# Power.net
KiCad netlist of a schematic drawn in Altium Designer
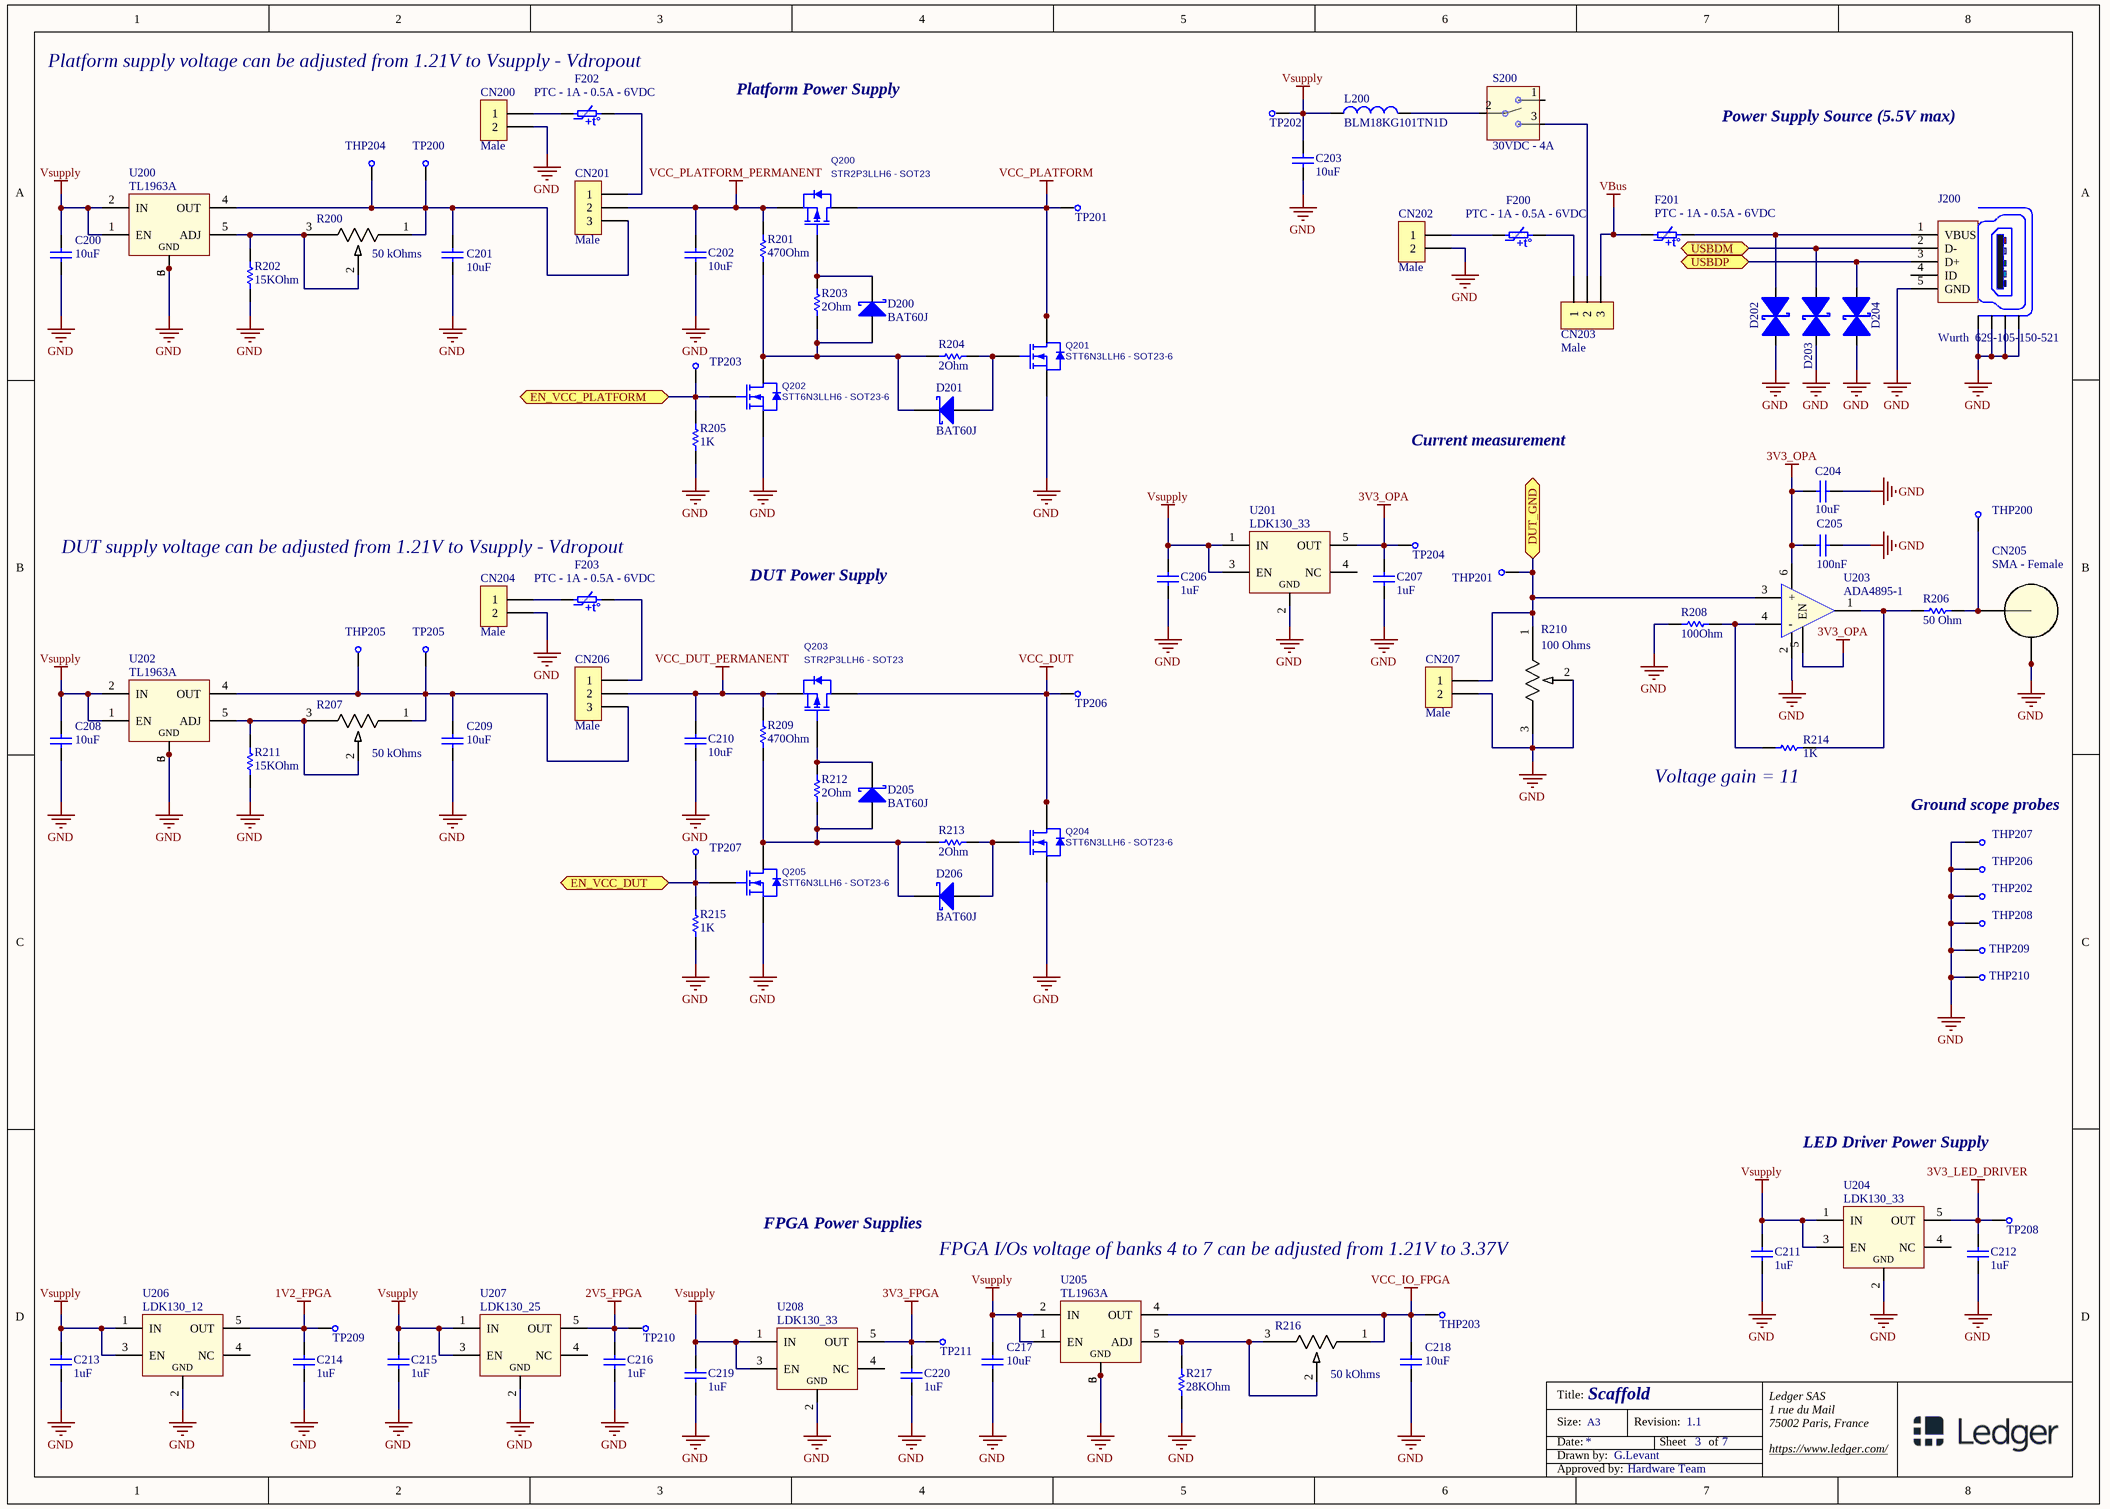
[diagram p0: Power.SchDoc]

(export (version "E")
  (design (tool "Eeschema 10.0.6"))
  (components
    (comp (ref "C200")
      (value "10uF")
      (footprint "CAP0603")
      (description "Capacitor 0603 - 10uF - 16V - X5R - 20%")
      (fields (field (name "MANUFACTURER") "Murata") (field (name "POWER") "16V"))
      (libsource (lib "Ledger_Prod") (part "Capacitor 0603 - 10uF - 16V - X5R - 20%"))
    )
    (comp (ref "C201")
      (value "10uF")
      (footprint "CAP0603")
      (description "Capacitor 0603 - 10uF - 16V - X5R - 20%")
      (fields (field (name "MANUFACTURER") "Murata") (field (name "POWER") "16V"))
      (libsource (lib "Ledger_Prod") (part "Capacitor 0603 - 10uF - 16V - X5R - 20%"))
    )
    (comp (ref "C202")
      (value "10uF")
      (footprint "CAP0603")
      (description "Capacitor 0603 - 10uF - 16V - X5R - 20%")
      (fields (field (name "MANUFACTURER") "Murata") (field (name "TOLERANCE") "20%"))
      (libsource (lib "Ledger_Prod") (part "Capacitor 0603 - 10uF - 16V - X5R - 20%"))
    )
    (comp (ref "C203")
      (value "10uF")
      (footprint "CAP0603")
      (description "Capacitor 0603 - 10uF - 16V - X5R - 20%")
      (fields (field (name "MANUFACTURER") "Murata") (field (name "TOLERANCE") "20%"))
      (libsource (lib "Ledger_Prod") (part "Capacitor 0603 - 10uF - 16V - X5R - 20%"))
    )
    (comp (ref "C204")
      (value "10uF")
      (footprint "CAP0603")
      (description "Capacitor 0603 - 10uF - 16V - X5R - 20%")
      (fields (field (name "MANUFACTURER") "Murata") (field (name "TOLERANCE") "20%"))
      (libsource (lib "Ledger_Prod") (part "Capacitor 0603 - 10uF - 16V - X5R - 20%"))
    )
    (comp (ref "C205")
      (value "100nF")
      (footprint "CAP0603")
      (description "Capacitor 0603 - 100nF - 16V - X7R - 10%")
      (fields (field (name "POWER") "16V") (field (name "TOLERANCE") "10%"))
      (libsource (lib "Ledger_Prod") (part "Capacitor 0603 - 100nF - 16V - X7R - 10%"))
    )
    (comp (ref "C206")
      (value "1uF")
      (footprint "CAP0603")
      (description "Capacitor 0603 - 1uF - 16V - X7R - 10%")
      (fields (field (name "MANUFACTURER") "Kemet") (field (name "POWER") "16V"))
      (libsource (lib "Ledger_Prod") (part "Capacitor 0603 -     1uF - 16V - X7R - 10%"))
    )
    (comp (ref "C207")
      (value "1uF")
      (footprint "CAP0603")
      (description "Capacitor 0603 - 1uF - 16V - X7R - 10%")
      (fields (field (name "MANUFACTURER") "Kemet") (field (name "POWER") "16V"))
      (libsource (lib "Ledger_Prod") (part "Capacitor 0603 -     1uF - 16V - X7R - 10%"))
    )
    (comp (ref "C208")
      (value "10uF")
      (footprint "CAP0603")
      (description "Capacitor 0603 - 10uF - 16V - X5R - 20%")
      (fields (field (name "MANUFACTURER") "Murata") (field (name "POWER") "16V"))
      (libsource (lib "Ledger_Prod") (part "Capacitor 0603 - 10uF - 16V - X5R - 20%"))
    )
    (comp (ref "C209")
      (value "10uF")
      (footprint "CAP0603")
      (description "Capacitor 0603 - 10uF - 16V - X5R - 20%")
      (fields (field (name "MANUFACTURER") "Murata") (field (name "POWER") "16V"))
      (libsource (lib "Ledger_Prod") (part "Capacitor 0603 - 10uF - 16V - X5R - 20%"))
    )
    (comp (ref "C210")
      (value "10uF")
      (footprint "CAP0603")
      (description "Capacitor 0603 - 10uF - 16V - X5R - 20%")
      (fields (field (name "MANUFACTURER") "Murata") (field (name "TOLERANCE") "20%"))
      (libsource (lib "Ledger_Prod") (part "Capacitor 0603 - 10uF - 16V - X5R - 20%"))
    )
    (comp (ref "C211")
      (value "1uF")
      (footprint "CAP0603")
      (description "Capacitor 0603 - 1uF - 16V - X7R - 10%")
      (fields (field (name "MANUFACTURER") "Kemet") (field (name "POWER") "16V"))
      (libsource (lib "Ledger_Prod") (part "Capacitor 0603 -     1uF - 16V - X7R - 10%"))
    )
    (comp (ref "C212")
      (value "1uF")
      (footprint "CAP0603")
      (description "Capacitor 0603 - 1uF - 16V - X7R - 10%")
      (fields (field (name "MANUFACTURER") "Kemet") (field (name "POWER") "16V"))
      (libsource (lib "Ledger_Prod") (part "Capacitor 0603 -     1uF - 16V - X7R - 10%"))
    )
    (comp (ref "C213")
      (value "1uF")
      (footprint "CAP0603")
      (description "Capacitor 0603 - 1uF - 16V - X7R - 10%")
      (fields (field (name "MANUFACTURER") "Kemet") (field (name "POWER") "16V"))
      (libsource (lib "Ledger_Prod") (part "Capacitor 0603 -     1uF - 16V - X7R - 10%"))
    )
    (comp (ref "C214")
      (value "1uF")
      (footprint "CAP0603")
      (description "Capacitor 0603 - 1uF - 16V - X7R - 10%")
      (fields (field (name "MANUFACTURER") "Kemet") (field (name "POWER") "16V"))
      (libsource (lib "Ledger_Prod") (part "Capacitor 0603 -     1uF - 16V - X7R - 10%"))
    )
    (comp (ref "C215")
      (value "1uF")
      (footprint "CAP0603")
      (description "Capacitor 0603 - 1uF - 16V - X7R - 10%")
      (fields (field (name "MANUFACTURER") "Kemet") (field (name "POWER") "16V"))
      (libsource (lib "Ledger_Prod") (part "Capacitor 0603 -     1uF - 16V - X7R - 10%"))
    )
    (comp (ref "C216")
      (value "1uF")
      (footprint "CAP0603")
      (description "Capacitor 0603 - 1uF - 16V - X7R - 10%")
      (fields (field (name "MANUFACTURER") "Kemet") (field (name "POWER") "16V"))
      (libsource (lib "Ledger_Prod") (part "Capacitor 0603 -     1uF - 16V - X7R - 10%"))
    )
    (comp (ref "C217")
      (value "10uF")
      (footprint "CAP0603")
      (description "Capacitor 0603 - 10uF - 16V - X5R - 20%")
      (fields (field (name "MANUFACTURER") "Murata") (field (name "POWER") "16V"))
      (libsource (lib "Ledger_Prod") (part "Capacitor 0603 - 10uF - 16V - X5R - 20%"))
    )
    (comp (ref "C218")
      (value "10uF")
      (footprint "CAP0603")
      (description "Capacitor 0603 - 10uF - 16V - X5R - 20%")
      (fields (field (name "MANUFACTURER") "Murata") (field (name "POWER") "16V"))
      (libsource (lib "Ledger_Prod") (part "Capacitor 0603 - 10uF - 16V - X5R - 20%"))
    )
    (comp (ref "C219")
      (value "1uF")
      (footprint "CAP0603")
      (description "Capacitor 0603 - 1uF - 16V - X7R - 10%")
      (fields (field (name "MANUFACTURER") "Kemet") (field (name "POWER") "16V"))
      (libsource (lib "Ledger_Prod") (part "Capacitor 0603 -     1uF - 16V - X7R - 10%"))
    )
    (comp (ref "C220")
      (value "1uF")
      (footprint "CAP0603")
      (description "Capacitor 0603 - 1uF - 16V - X7R - 10%")
      (fields (field (name "MANUFACTURER") "Kemet") (field (name "POWER") "16V"))
      (libsource (lib "Ledger_Prod") (part "Capacitor 0603 -     1uF - 16V - X7R - 10%"))
    )
    (comp (ref "CN200")
      (value "Male")
      (footprint "WURTH_691213710002")
      (description "Connector - Wire to Board Terminal Block - 2-Positions - Wurth - 691213710002")
      (fields (field (name "MANUFACTURER") "Wurth"))
      (libsource (lib "Ledger_Dev") (part "Connector - Wire to Board Terminal Block - 2-Positions - Wurth - 691213710002"))
    )
    (comp (ref "CN201")
      (value "Male")
      (footprint "MOLEX_90120-0123")
      (description "Connector - Header - 3-Pin - single row - Male - Molex_90120-0123")
      (fields (field (name "MANUFACTURER") "Molex"))
      (libsource (lib "Ledger_Dev") (part "Connector - Header - 3-Pin - single row - Male - Molex_90120-0123"))
    )
    (comp (ref "CN202")
      (value "Male")
      (footprint "WURTH_691213710002")
      (description "Connector - Wire to Board Terminal Block - 2-Positions - Wurth - 691213710002")
      (fields (field (name "MANUFACTURER") "Wurth"))
      (libsource (lib "Ledger_Dev") (part "Connector - Wire to Board Terminal Block - 2-Positions - Wurth - 691213710002"))
    )
    (comp (ref "CN203")
      (value "Male")
      (footprint "MOLEX_90120-0123")
      (description "Connector - Header - 3-Pin - single row - Male - Molex_90120-0123")
      (fields (field (name "MANUFACTURER") "Molex"))
      (libsource (lib "") (part "Connector - Header - 3-Pin - single row - Male - Molex_90120-0123_1"))
    )
    (comp (ref "CN204")
      (value "Male")
      (footprint "WURTH_691213710002")
      (description "Connector - Wire to Board Terminal Block - 2-Positions - Wurth - 691213710002")
      (fields (field (name "MANUFACTURER") "Wurth"))
      (libsource (lib "Ledger_Dev") (part "Connector - Wire to Board Terminal Block - 2-Positions - Wurth - 691213710002"))
    )
    (comp (ref "CN205")
      (value "SMA - Female")
      (footprint "SAMTEC_SMA-J-P-X-ST-EM3")
      (description "Connector - SMA - Female - Horizontal - Mid Mount - Samtec - SMA–J–P–H–ST–EM3")
      (fields (field (name "MANUFACTURER") "Samtec"))
      (libsource (lib "Ledger_Dev") (part "Connector - SMA - Female - Horizontal - Mid Mount - Samtec - SMA–J–P–H–ST–EM3"))
    )
    (comp (ref "CN206")
      (value "Male")
      (footprint "MOLEX_90120-0123")
      (description "Connector - Header - 3-Pin - single row - Male - Molex_90120-0123")
      (fields (field (name "MANUFACTURER") "Molex"))
      (libsource (lib "Ledger_Dev") (part "Connector - Header - 3-Pin - single row - Male - Molex_90120-0123"))
    )
    (comp (ref "CN207")
      (value "Male")
      (footprint "MOLEX_90120-0122")
      (description "Connector - Header - 2-Pin - single row - Male - Molex")
      (fields (field (name "MANUFACTURER") "Molex"))
      (libsource (lib "Ledger_Dev") (part "Connector - Header - 2-Pin - single row - Male - Molex"))
    )
    (comp (ref "D200")
      (value "BAT60J")
      (footprint "SOD323/A")
      (fields (field (name "MANUFACTURER") "STMicroelectronics") (field (name "POWER") "310mW"))
      (libsource (lib "Ledger_Dev") (part "Diode -Schottky -10V - 3 A - SOD−323 - BAT60J"))
    )
    (comp (ref "D201")
      (value "BAT60J")
      (footprint "SOD323/A")
      (fields (field (name "MANUFACTURER") "STMicroelectronics") (field (name "POWER") "310mW"))
      (libsource (lib "Ledger_Dev") (part "Diode -Schottky -10V - 3 A - SOD−323 - BAT60J"))
    )
    (comp (ref "D202")
      (value "ESDAXLC6-1BT2")
      (footprint "SOD882")
      (description "Diode - ESD -15kV -10GHz - ESDAXLC6-1BT2")
      (fields (field (name "MANUFACTURER") "STMicroelectronics"))
      (libsource (lib "Ledger_Dev") (part "Diode - ESD -15kV -10GHz - ESDAXLC6-1BT2"))
    )
    (comp (ref "D203")
      (value "ESDAXLC6-1BT2")
      (footprint "SOD882")
      (description "Diode - ESD -15kV -10GHz - ESDAXLC6-1BT2")
      (fields (field (name "MANUFACTURER") "STMicroelectronics"))
      (libsource (lib "Ledger_Dev") (part "Diode - ESD -15kV -10GHz - ESDAXLC6-1BT2"))
    )
    (comp (ref "D204")
      (value "ESDAXLC6-1BT2")
      (footprint "SOD882")
      (description "Diode - ESD -15kV -10GHz - ESDAXLC6-1BT2")
      (fields (field (name "MANUFACTURER") "STMicroelectronics"))
      (libsource (lib "Ledger_Dev") (part "Diode - ESD -15kV -10GHz - ESDAXLC6-1BT2"))
    )
    (comp (ref "D205")
      (value "BAT60J")
      (footprint "SOD323/A")
      (fields (field (name "MANUFACTURER") "STMicroelectronics") (field (name "POWER") "310mW"))
      (libsource (lib "Ledger_Dev") (part "Diode -Schottky -10V - 3 A - SOD−323 - BAT60J"))
    )
    (comp (ref "D206")
      (value "BAT60J")
      (footprint "SOD323/A")
      (fields (field (name "MANUFACTURER") "STMicroelectronics") (field (name "POWER") "310mW"))
      (libsource (lib "Ledger_Dev") (part "Diode -Schottky -10V - 3 A - SOD−323 - BAT60J"))
    )
    (comp (ref "F200")
      (value "PTC - 1A - 0.5A - 6VDC")
      (footprint "FUSE_0805")
      (description "Fuse 0805 - PTC Resettable - 1A - 0.5A - 6VDC - 0.9Ohms")
      (fields (field (name "VOLTAGE") "6V") (field (name "MANUFACTURER") "Bel Fuse"))
      (libsource (lib "Ledger_Dev") (part "Fuse 0805 - PTC Resettable - 1A - 0.5A - 6VDC - 0.9Ohms"))
    )
    (comp (ref "F201")
      (value "PTC - 1A - 0.5A - 6VDC")
      (footprint "FUSE_0805")
      (description "Fuse 0805 - PTC Resettable - 1A - 0.5A - 6VDC - 0.9Ohms")
      (fields (field (name "VOLTAGE") "6V") (field (name "MANUFACTURER") "Bel Fuse"))
      (libsource (lib "Ledger_Dev") (part "Fuse 0805 - PTC Resettable - 1A - 0.5A - 6VDC - 0.9Ohms"))
    )
    (comp (ref "F202")
      (value "PTC - 1A - 0.5A - 6VDC")
      (footprint "FUSE_0805")
      (description "Fuse 0805 - PTC Resettable - 1A - 0.5A - 6VDC - 0.9Ohms")
      (fields (field (name "VOLTAGE") "6V") (field (name "MANUFACTURER") "Bel Fuse"))
      (libsource (lib "Ledger_Dev") (part "Fuse 0805 - PTC Resettable - 1A - 0.5A - 6VDC - 0.9Ohms"))
    )
    (comp (ref "F203")
      (value "PTC - 1A - 0.5A - 6VDC")
      (footprint "FUSE_0805")
      (description "Fuse 0805 - PTC Resettable - 1A - 0.5A - 6VDC - 0.9Ohms")
      (fields (field (name "VOLTAGE") "6V") (field (name "MANUFACTURER") "Bel Fuse"))
      (libsource (lib "Ledger_Dev") (part "Fuse 0805 - PTC Resettable - 1A - 0.5A - 6VDC - 0.9Ohms"))
    )
    (comp (ref "J200")
      (value "Wurth  629-105-150-521")
      (footprint "629105150521")
      (description "Connector - USB - Micro B - Wurth")
      (fields (field (name "MANUFACTURER") "Wurth"))
      (libsource (lib "Ledger_Prod") (part "Connector - USB - Micro B - Wurth"))
    )
    (comp (ref "L200")
      (value "BLM18KG101TN1D")
      (footprint "0603")
      (description "Ferrite - Bead - 0603 BLM18")
      (fields (field (name "MANUFACTURER") "MURATA"))
      (libsource (lib "Ledger_Dev") (part "Ferrite - Bead - 0603 BLM18"))
    )
    (comp (ref "Logo200")
      (value "Misc - Logo Increase clockwise")
      (footprint "LOGO_CLOCKWISE_INCREASE")
      (libsource (lib "Ledger_Dev") (part "Misc - Logo Increase clockwise"))
    )
    (comp (ref "Logo201")
      (value "Misc - Logo Increase clockwise")
      (footprint "LOGO_CLOCKWISE_INCREASE")
      (libsource (lib "Ledger_Dev") (part "Misc - Logo Increase clockwise"))
    )
    (comp (ref "Logo202")
      (value "Misc - Logo Increase clockwise")
      (footprint "LOGO_CLOCKWISE_INCREASE")
      (libsource (lib "Ledger_Dev") (part "Misc - Logo Increase clockwise"))
    )
    (comp (ref "Logo203")
      (value "Misc - Logo Increase clockwise")
      (footprint "LOGO_CLOCKWISE_INCREASE")
      (libsource (lib "Ledger_Dev") (part "Misc - Logo Increase clockwise"))
    )
    (comp (ref "Q200")
      (value "STR2P3LLH6 - SOT23")
      (footprint "SOT23")
      (description "Switch - PMOS 30V - STR2P3LLH6 - SOT23")
      (fields (field (name "MANUFACTURER") "STMicroelectronics"))
      (libsource (lib "Ledger_Dev") (part "Switch - PMOS 30V - STR2P3LLH6 - SOT23"))
    )
    (comp (ref "Q201")
      (value "STT6N3LLH6 - SOT23-6")
      (footprint "SOT95P280X145-6N")
      (description "Switch - NMOS 30V - STT6N3LLH6 - SOT23-6")
      (fields (field (name "MANUFACTURER") "STMicroelectronics"))
      (libsource (lib "Ledger_Dev") (part "Switch - NMOS 30V - STT6N3LLH6 - SOT23-6"))
    )
    (comp (ref "Q202")
      (value "STT6N3LLH6 - SOT23-6")
      (footprint "SOT95P280X145-6N")
      (description "Switch - NMOS 30V - STT6N3LLH6 - SOT23-6")
      (fields (field (name "MANUFACTURER") "STMicroelectronics"))
      (libsource (lib "Ledger_Dev") (part "Switch - NMOS 30V - STT6N3LLH6 - SOT23-6"))
    )
    (comp (ref "Q203")
      (value "STR2P3LLH6 - SOT23")
      (footprint "SOT23")
      (description "Switch - PMOS 30V - STR2P3LLH6 - SOT23")
      (fields (field (name "MANUFACTURER") "STMicroelectronics"))
      (libsource (lib "Ledger_Dev") (part "Switch - PMOS 30V - STR2P3LLH6 - SOT23"))
    )
    (comp (ref "Q204")
      (value "STT6N3LLH6 - SOT23-6")
      (footprint "SOT95P280X145-6N")
      (description "Switch - NMOS 30V - STT6N3LLH6 - SOT23-6")
      (fields (field (name "MANUFACTURER") "STMicroelectronics"))
      (libsource (lib "Ledger_Dev") (part "Switch - NMOS 30V - STT6N3LLH6 - SOT23-6"))
    )
    (comp (ref "Q205")
      (value "STT6N3LLH6 - SOT23-6")
      (footprint "SOT95P280X145-6N")
      (description "Switch - NMOS 30V - STT6N3LLH6 - SOT23-6")
      (fields (field (name "MANUFACTURER") "STMicroelectronics"))
      (libsource (lib "Ledger_Dev") (part "Switch - NMOS 30V - STT6N3LLH6 - SOT23-6"))
    )
    (comp (ref "R200")
      (value "50 kOhms")
      (footprint "POT_3296W")
      (description "Potentiometer - 50 kOhms - 10% - 0.5W - Bourns - 3296W-1-503RLF")
      (fields (field (name "MANUFACTURER") "Bourns Electronics") (field (name "POWER") "0.5W"))
      (libsource (lib "Ledger_Prod") (part "Potentiometer - 50 kOhms - 10% - 0.5W - Bourns - 3296W-1-503RLF"))
    )
    (comp (ref "R201")
      (value "470Ohm")
      (footprint "RES0603")
      (description "Resistor 0603 -    470Ohm - 1/10W - 1%")
      (fields (field (name "TOLERANCE") "1%") (field (name "POWER") "1/10W"))
      (libsource (lib "Ledger_Prod") (part "Resistor 0603 -    470Ohm - 1/10W - 1%"))
    )
    (comp (ref "R202")
      (value "15KOhm")
      (footprint "RES0603")
      (description "Resistor 0603 -    15KOhm - 1/10W - 1%")
      (fields (field (name "TOLERANCE") "1%") (field (name "POWER") "1/10W"))
      (libsource (lib "Ledger_Prod") (part "Resistor 0603 -    15KOhm - 1/10W - 1%"))
    )
    (comp (ref "R203")
      (value "2Ohm")
      (footprint "RES0603")
      (description "Resistor 0603 - 2Ohm - 1/10W - 1%")
      (fields (field (name "TOLERANCE") "1%") (field (name "POWER") "1/10W"))
      (libsource (lib "Ledger_Prod") (part "Resistor 0603 -      2Ohm - 1/10W - 1%"))
    )
    (comp (ref "R204")
      (value "2Ohm")
      (footprint "RES0603")
      (description "Resistor 0603 - 2Ohm - 1/10W - 1%")
      (fields (field (name "TOLERANCE") "1%") (field (name "POWER") "1/10W"))
      (libsource (lib "Ledger_Prod") (part "Resistor 0603 -      2Ohm - 1/10W - 1%"))
    )
    (comp (ref "R205")
      (value "1K")
      (footprint "RES0603")
      (description "Resistor 0603 - 1KOhm - 1/10W - 1%")
      (fields (field (name "TOLERANCE") "1%") (field (name "POWER") "1/10W"))
      (libsource (lib "Ledger_Prod") (part "Resistor 0603 -      1KOhm - 1/10W - 1%"))
    )
    (comp (ref "R206")
      (value "50 Ohm")
      (footprint "RES0603")
      (description "Resistor 0603 -  50Ohm - 1/10W - 1%")
      (fields (field (name "POWER") "1/10W") (field (name "TOLERANCE") "1%"))
      (libsource (lib "Ledger_Prod") (part "Resistor 0603 -  50Ohm - 1/10W - 1%"))
    )
    (comp (ref "R207")
      (value "50 kOhms")
      (footprint "POT_3296W")
      (description "Potentiometer - 50 kOhms - 10% - 0.5W - Bourns - 3296W-1-503RLF")
      (fields (field (name "MANUFACTURER") "Bourns Electronics") (field (name "POWER") "0.5W"))
      (libsource (lib "Ledger_Prod") (part "Potentiometer - 50 kOhms - 10% - 0.5W - Bourns - 3296W-1-503RLF"))
    )
    (comp (ref "R208")
      (value "100Ohm")
      (footprint "RES0603")
      (description "Resistor 0603 -    100Ohm - 1/10W - 1%")
      (fields (field (name "TOLERANCE") "1%") (field (name "POWER") "1/10W"))
      (libsource (lib "Ledger_Prod") (part "Resistor 0603 -    100Ohm - 1/10W - 1%"))
    )
    (comp (ref "R209")
      (value "470Ohm")
      (footprint "RES0603")
      (description "Resistor 0603 -    470Ohm - 1/10W - 1%")
      (fields (field (name "TOLERANCE") "1%") (field (name "POWER") "1/10W"))
      (libsource (lib "Ledger_Prod") (part "Resistor 0603 -    470Ohm - 1/10W - 1%"))
    )
    (comp (ref "R210")
      (value "100 Ohms")
      (footprint "POT_3296W")
      (description "Potentiometer - 100 Ohms - 25 turns - 10% - 0.5W - Bourns - 3296W-1-101LF")
      (fields (field (name "MANUFACTURER") "Bourns Electronics") (field (name "POWER") "0.5W"))
      (libsource (lib "Ledger_Prod") (part "Potentiometer - 100 Ohms - 25 turns - 10% - 0.5W - Bourns - 3296W-1-101LF"))
    )
    (comp (ref "R211")
      (value "15KOhm")
      (footprint "RES0603")
      (description "Resistor 0603 -    15KOhm - 1/10W - 1%")
      (fields (field (name "TOLERANCE") "1%") (field (name "POWER") "1/10W"))
      (libsource (lib "Ledger_Prod") (part "Resistor 0603 -    15KOhm - 1/10W - 1%"))
    )
    (comp (ref "R212")
      (value "2Ohm")
      (footprint "RES0603")
      (description "Resistor 0603 - 2Ohm - 1/10W - 1%")
      (fields (field (name "TOLERANCE") "1%") (field (name "POWER") "1/10W"))
      (libsource (lib "Ledger_Prod") (part "Resistor 0603 -      2Ohm - 1/10W - 1%"))
    )
    (comp (ref "R213")
      (value "2Ohm")
      (footprint "RES0603")
      (description "Resistor 0603 - 2Ohm - 1/10W - 1%")
      (fields (field (name "TOLERANCE") "1%") (field (name "POWER") "1/10W"))
      (libsource (lib "Ledger_Prod") (part "Resistor 0603 -      2Ohm - 1/10W - 1%"))
    )
    (comp (ref "R214")
      (value "1K")
      (footprint "RES0603")
      (description "Resistor 0603 - 1KOhm - 1/10W - 1%")
      (fields (field (name "TOLERANCE") "1%") (field (name "POWER") "1/10W"))
      (libsource (lib "Ledger_Prod") (part "Resistor 0603 -      1KOhm - 1/10W - 1%"))
    )
    (comp (ref "R215")
      (value "1K")
      (footprint "RES0603")
      (description "Resistor 0603 - 1KOhm - 1/10W - 1%")
      (fields (field (name "TOLERANCE") "1%") (field (name "POWER") "1/10W"))
      (libsource (lib "Ledger_Prod") (part "Resistor 0603 -      1KOhm - 1/10W - 1%"))
    )
    (comp (ref "R216")
      (value "50 kOhms")
      (footprint "POT_3296W")
      (description "Potentiometer - 50 kOhms - 10% - 0.5W - Bourns - 3296W-1-503RLF")
      (fields (field (name "MANUFACTURER") "Bourns Electronics") (field (name "POWER") "0.5W"))
      (libsource (lib "Ledger_Prod") (part "Potentiometer - 50 kOhms - 10% - 0.5W - Bourns - 3296W-1-503RLF"))
    )
    (comp (ref "R217")
      (value "28KOhm")
      (footprint "RES0603")
      (description "Resistor 0603 -    28KOhm - 1/10W - 1%")
      (fields (field (name "TOLERANCE") "1%") (field (name "POWER") "1/10W"))
      (libsource (lib "Ledger_Prod") (part "Resistor 0603 -    28KOhm - 1/10W - 1%"))
    )
    (comp (ref "S200")
      (value "30VDC - 4A")
      (footprint "SWITCH_25136NAH")
      (description "Slide switch - 4A - 30VDC - APEM - 25136NAH")
      (fields (field (name "MANUFACTURER") "APEM"))
      (libsource (lib "Ledger_Dev") (part "Slide switch - 4A - 30VDC - APEM - 25136NAH"))
    )
    (comp (ref "THP200")
      (value "Misc - Test pin - Through hole - Millmax - 6821-0-00-15-00-00-08-0")
      (footprint "MILLMAX_6821-0-00-15-00-00-08-0")
      (fields (field (name "MANUFACTURER") "Mill-max"))
      (libsource (lib "Ledger_Dev") (part "Misc - Test pin - Through hole - Millmax - 6821-0-00-15-00-00-08-0"))
    )
    (comp (ref "THP201")
      (value "Misc - Test pin - Through hole - Millmax - 6821-0-00-15-00-00-08-0")
      (footprint "MILLMAX_6821-0-00-15-00-00-08-0")
      (fields (field (name "MANUFACTURER") "Mill-max"))
      (libsource (lib "Ledger_Dev") (part "Misc - Test pin - Through hole - Millmax - 6821-0-00-15-00-00-08-0"))
    )
    (comp (ref "THP202")
      (value "Misc - Test pin - Through hole - Millmax - 6821-0-00-15-00-00-08-0")
      (footprint "MILLMAX_6821-0-00-15-00-00-08-0")
      (fields (field (name "MANUFACTURER") "Mill-max"))
      (libsource (lib "Ledger_Dev") (part "Misc - Test pin - Through hole - Millmax - 6821-0-00-15-00-00-08-0"))
    )
    (comp (ref "THP203")
      (value "Misc - Test pin - Through hole - Millmax - 6821-0-00-15-00-00-08-0")
      (footprint "MILLMAX_6821-0-00-15-00-00-08-0")
      (fields (field (name "MANUFACTURER") "Mill-max"))
      (libsource (lib "Ledger_Dev") (part "Misc - Test pin - Through hole - Millmax - 6821-0-00-15-00-00-08-0"))
    )
    (comp (ref "THP204")
      (value "Misc - Test pin - Through hole - Millmax - 6821-0-00-15-00-00-08-0")
      (footprint "MILLMAX_6821-0-00-15-00-00-08-0")
      (fields (field (name "MANUFACTURER") "Mill-max"))
      (libsource (lib "Ledger_Dev") (part "Misc - Test pin - Through hole - Millmax - 6821-0-00-15-00-00-08-0"))
    )
    (comp (ref "THP205")
      (value "Misc - Test pin - Through hole - Millmax - 6821-0-00-15-00-00-08-0")
      (footprint "MILLMAX_6821-0-00-15-00-00-08-0")
      (fields (field (name "MANUFACTURER") "Mill-max"))
      (libsource (lib "Ledger_Dev") (part "Misc - Test pin - Through hole - Millmax - 6821-0-00-15-00-00-08-0"))
    )
    (comp (ref "THP206")
      (value "Misc - Test pin - Through hole - Millmax - 6821-0-00-15-00-00-08-0")
      (footprint "MILLMAX_6821-0-00-15-00-00-08-0")
      (fields (field (name "MANUFACTURER") "Mill-max"))
      (libsource (lib "Ledger_Dev") (part "Misc - Test pin - Through hole - Millmax - 6821-0-00-15-00-00-08-0"))
    )
    (comp (ref "THP207")
      (value "Misc - Test pin - Through hole - Millmax - 6821-0-00-15-00-00-08-0")
      (footprint "MILLMAX_6821-0-00-15-00-00-08-0")
      (fields (field (name "MANUFACTURER") "Mill-max"))
      (libsource (lib "Ledger_Dev") (part "Misc - Test pin - Through hole - Millmax - 6821-0-00-15-00-00-08-0"))
    )
    (comp (ref "THP208")
      (value "Misc - Test pin - Through hole - Millmax - 6821-0-00-15-00-00-08-0")
      (footprint "MILLMAX_6821-0-00-15-00-00-08-0")
      (fields (field (name "MANUFACTURER") "Mill-max"))
      (libsource (lib "Ledger_Dev") (part "Misc - Test pin - Through hole - Millmax - 6821-0-00-15-00-00-08-0"))
    )
    (comp (ref "THP209")
      (value "Misc - Test pin - Through hole - Millmax - 6821-0-00-15-00-00-08-0")
      (footprint "MILLMAX_6821-0-00-15-00-00-08-0")
      (fields (field (name "MANUFACTURER") "Mill-max"))
      (libsource (lib "Ledger_Dev") (part "Misc - Test pin - Through hole - Millmax - 6821-0-00-15-00-00-08-0"))
    )
    (comp (ref "THP210")
      (value "Misc - Test pin - Through hole - Millmax - 6821-0-00-15-00-00-08-0")
      (footprint "MILLMAX_6821-0-00-15-00-00-08-0")
      (fields (field (name "MANUFACTURER") "Mill-max"))
      (libsource (lib "Ledger_Dev") (part "Misc - Test pin - Through hole - Millmax - 6821-0-00-15-00-00-08-0"))
    )
    (comp (ref "TP200")
      (value "~")
      (footprint "TP_001")
      (description "Misc - Test point CMS")
      (libsource (lib "Ledger_Dev") (part "Misc - Test point CMS"))
    )
    (comp (ref "TP201")
      (value "~")
      (footprint "TP_001")
      (description "Misc - Test point CMS")
      (libsource (lib "Ledger_Dev") (part "Misc - Test point CMS"))
    )
    (comp (ref "TP202")
      (value "~")
      (footprint "TP_001")
      (description "Misc - Test point CMS")
      (libsource (lib "Ledger_Dev") (part "Misc - Test point CMS"))
    )
    (comp (ref "TP203")
      (value "~")
      (footprint "TP_001")
      (description "Misc - Test point CMS")
      (libsource (lib "Ledger_Dev") (part "Misc - Test point CMS"))
    )
    (comp (ref "TP204")
      (value "~")
      (footprint "TP_001")
      (description "Misc - Test point CMS")
      (libsource (lib "Ledger_Dev") (part "Misc - Test point CMS"))
    )
    (comp (ref "TP205")
      (value "~")
      (footprint "TP_001")
      (description "Misc - Test point CMS")
      (libsource (lib "Ledger_Dev") (part "Misc - Test point CMS"))
    )
    (comp (ref "TP206")
      (value "~")
      (footprint "TP_001")
      (description "Misc - Test point CMS")
      (libsource (lib "Ledger_Dev") (part "Misc - Test point CMS"))
    )
    (comp (ref "TP207")
      (value "~")
      (footprint "TP_001")
      (description "Misc - Test point CMS")
      (libsource (lib "Ledger_Dev") (part "Misc - Test point CMS"))
    )
    (comp (ref "TP208")
      (value "~")
      (footprint "TP_001")
      (description "Misc - Test point CMS")
      (libsource (lib "Ledger_Dev") (part "Misc - Test point CMS"))
    )
    (comp (ref "TP209")
      (value "~")
      (footprint "TP_001")
      (description "Misc - Test point CMS")
      (libsource (lib "Ledger_Dev") (part "Misc - Test point CMS"))
    )
    (comp (ref "TP210")
      (value "~")
      (footprint "TP_001")
      (description "Misc - Test point CMS")
      (libsource (lib "Ledger_Dev") (part "Misc - Test point CMS"))
    )
    (comp (ref "TP211")
      (value "~")
      (footprint "TP_001")
      (description "Misc - Test point CMS")
      (libsource (lib "Ledger_Dev") (part "Misc - Test point CMS"))
    )
    (comp (ref "U200")
      (value "TL1963A")
      (footprint "SOT223-6")
      (description "Power - LDO - Adj - 20V - 1.5A - SOT223-6")
      (fields (field (name "MANUFACTURER") "Texas Instruments") (field (name "POWER") "1.5A"))
      (libsource (lib "Ledger_Dev") (part "Power - LDO - Adj - 20V - 1.5A - SOT223-6"))
    )
    (comp (ref "U201")
      (value "LDK130_33")
      (footprint "SOT95P280X145-5L30")
      (description "Power - LDO - 3.3V - 300 mA - SOT23-5L")
      (fields (field (name "MANUFACTURER") "STMicroelectronics") (field (name "POWER") "300mA"))
      (libsource (lib "Ledger_Dev") (part "Power - LDO - 3.3V - 300 mA - SOT23-5L"))
    )
    (comp (ref "U202")
      (value "TL1963A")
      (footprint "SOT223-6")
      (description "Power - LDO - Adj - 20V - 1.5A - SOT223-6")
      (fields (field (name "MANUFACTURER") "Texas Instruments") (field (name "POWER") "1.5A"))
      (libsource (lib "Ledger_Dev") (part "Power - LDO - Adj - 20V - 1.5A - SOT223-6"))
    )
    (comp (ref "U203")
      (value "ADA4895-1")
      (footprint "SOT95P280X145-6N")
      (description "Power - Operationnal amplifier - ADA4895-1")
      (fields (field (name "MANUFACTURER") "Analog Device"))
      (libsource (lib "Ledger_Dev") (part "Power - Operationnal amplifier - ADA4895-1"))
    )
    (comp (ref "U204")
      (value "LDK130_33")
      (footprint "SOT95P280X145-5L30")
      (description "Power - LDO - 3.3V - 300 mA - SOT23-5L")
      (fields (field (name "MANUFACTURER") "STMicroelectronics") (field (name "POWER") "300mA"))
      (libsource (lib "Ledger_Dev") (part "Power - LDO - 3.3V - 300 mA - SOT23-5L"))
    )
    (comp (ref "U205")
      (value "TL1963A")
      (footprint "SOT223-6")
      (description "Power - LDO - Adj - 20V - 1.5A - SOT223-6")
      (fields (field (name "MANUFACTURER") "Texas Instruments") (field (name "POWER") "1.5A"))
      (libsource (lib "Ledger_Dev") (part "Power - LDO - Adj - 20V - 1.5A - SOT223-6"))
    )
    (comp (ref "U206")
      (value "LDK130_12")
      (footprint "SOT95P280X145-5L30")
      (description "Power - LDO - 1.2V - 300 mA - SOT23-5L")
      (fields (field (name "MANUFACTURER") "STMicroelectronics") (field (name "POWER") "300mA"))
      (libsource (lib "Ledger_Dev") (part "Power - LDO - 1.2V - 300 mA - SOT23-5L"))
    )
    (comp (ref "U207")
      (value "LDK130_25")
      (footprint "SOT95P280X145-5L30")
      (description "Power - LDO - 2.5V - 300 mA - SOT23-5L")
      (fields (field (name "MANUFACTURER") "STMicroelectronics") (field (name "POWER") "300mA"))
      (libsource (lib "Ledger_Dev") (part "Power - LDO - 2.5V - 300 mA - SOT23-5L"))
    )
    (comp (ref "U208")
      (value "LDK130_33")
      (footprint "SOT95P280X145-5L30")
      (description "Power - LDO - 3.3V - 300 mA - SOT23-5L")
      (fields (field (name "MANUFACTURER") "STMicroelectronics") (field (name "POWER") "300mA"))
      (libsource (lib "Ledger_Dev") (part "Power - LDO - 3.3V - 300 mA - SOT23-5L"))
    )
  )
  (nets
    (net (code "1") (name "/DUT_GND") (class "Default")
      (node (ref "CN207") (pin "1") (pinfunction "1_1") (pintype "passive"))
      (node (ref "R210") (pin "1") (pinfunction "1_1") (pintype "passive"))
      (node (ref "THP201") (pin "1") (pinfunction "1_1") (pintype "passive"))
      (node (ref "U203") (pin "3") (pinfunction "+_3") (pintype "passive"))
    )
    (net (code "2") (name "/EN_VCC_DUT") (class "Default")
      (node (ref "Q205") (pin "3") (pinfunction "G_3") (pintype "passive"))
      (node (ref "R215") (pin "2") (pinfunction "2_2") (pintype "passive"))
      (node (ref "TP207") (pin "1") (pinfunction "1_1") (pintype "passive"))
    )
    (net (code "3") (name "/EN_VCC_PLATFORM") (class "Default")
      (node (ref "Q202") (pin "3") (pinfunction "G_3") (pintype "passive"))
      (node (ref "R205") (pin "2") (pinfunction "2_2") (pintype "passive"))
      (node (ref "TP203") (pin "1") (pinfunction "1_1") (pintype "passive"))
    )
    (net (code "4") (name "/USBDM") (class "Default")
      (node (ref "D203") (pin "C") (pinfunction "K_C") (pintype "passive"))
      (node (ref "J200") (pin "2") (pinfunction "D-_2") (pintype "passive"))
    )
    (net (code "5") (name "/USBDP") (class "Default")
      (node (ref "D204") (pin "C") (pinfunction "K_C") (pintype "passive"))
      (node (ref "J200") (pin "3") (pinfunction "D+_3") (pintype "passive"))
    )
    (net (code "6") (name "1V2_FPGA") (class "Default")
      (node (ref "C214") (pin "2") (pinfunction "2_2") (pintype "passive"))
      (node (ref "TP209") (pin "1") (pinfunction "1_1") (pintype "passive"))
      (node (ref "U206") (pin "5") (pinfunction "OUT_5") (pintype "passive"))
    )
    (net (code "7") (name "2V5_FPGA") (class "Default")
      (node (ref "C216") (pin "2") (pinfunction "2_2") (pintype "passive"))
      (node (ref "TP210") (pin "1") (pinfunction "1_1") (pintype "passive"))
      (node (ref "U207") (pin "5") (pinfunction "OUT_5") (pintype "passive"))
    )
    (net (code "8") (name "3V3_FPGA") (class "Default")
      (node (ref "C220") (pin "2") (pinfunction "2_2") (pintype "passive"))
      (node (ref "TP211") (pin "1") (pinfunction "1_1") (pintype "passive"))
      (node (ref "U208") (pin "5") (pinfunction "OUT_5") (pintype "passive"))
    )
    (net (code "9") (name "3V3_LED_DRIVER") (class "Default")
      (node (ref "C212") (pin "2") (pinfunction "2_2") (pintype "passive"))
      (node (ref "TP208") (pin "1") (pinfunction "1_1") (pintype "passive"))
      (node (ref "U204") (pin "5") (pinfunction "OUT_5") (pintype "passive"))
    )
    (net (code "10") (name "3V3_OPA") (class "Default")
      (node (ref "C204") (pin "1") (pinfunction "1_1") (pintype "passive"))
      (node (ref "C205") (pin "1") (pinfunction "1_1") (pintype "passive"))
      (node (ref "C207") (pin "2") (pinfunction "2_2") (pintype "passive"))
      (node (ref "TP204") (pin "1") (pinfunction "1_1") (pintype "passive"))
      (node (ref "U201") (pin "5") (pinfunction "OUT_5") (pintype "passive"))
      (node (ref "U203") (pin "5") (pinfunction "EN_5") (pintype "passive"))
      (node (ref "U203") (pin "6") (pinfunction "VS+_6") (pintype "passive"))
    )
    (net (code "11") (name "GND") (class "Default")
      (node (ref "C200") (pin "1") (pinfunction "1_1") (pintype "passive"))
      (node (ref "C201") (pin "1") (pinfunction "1_1") (pintype "passive"))
      (node (ref "C202") (pin "1") (pinfunction "1_1") (pintype "passive"))
      (node (ref "C203") (pin "1") (pinfunction "1_1") (pintype "passive"))
      (node (ref "C204") (pin "2") (pinfunction "2_2") (pintype "passive"))
      (node (ref "C205") (pin "2") (pinfunction "2_2") (pintype "passive"))
      (node (ref "C206") (pin "1") (pinfunction "1_1") (pintype "passive"))
      (node (ref "C207") (pin "1") (pinfunction "1_1") (pintype "passive"))
      (node (ref "C208") (pin "1") (pinfunction "1_1") (pintype "passive"))
      (node (ref "C209") (pin "1") (pinfunction "1_1") (pintype "passive"))
      (node (ref "C210") (pin "1") (pinfunction "1_1") (pintype "passive"))
      (node (ref "C211") (pin "1") (pinfunction "1_1") (pintype "passive"))
      (node (ref "C212") (pin "1") (pinfunction "1_1") (pintype "passive"))
      (node (ref "C213") (pin "1") (pinfunction "1_1") (pintype "passive"))
      (node (ref "C214") (pin "1") (pinfunction "1_1") (pintype "passive"))
      (node (ref "C215") (pin "1") (pinfunction "1_1") (pintype "passive"))
      (node (ref "C216") (pin "1") (pinfunction "1_1") (pintype "passive"))
      (node (ref "C217") (pin "1") (pinfunction "1_1") (pintype "passive"))
      (node (ref "C218") (pin "1") (pinfunction "1_1") (pintype "passive"))
      (node (ref "C219") (pin "1") (pinfunction "1_1") (pintype "passive"))
      (node (ref "C220") (pin "1") (pinfunction "1_1") (pintype "passive"))
      (node (ref "CN200") (pin "2") (pinfunction "2_2") (pintype "passive"))
      (node (ref "CN202") (pin "2") (pinfunction "2_2") (pintype "passive"))
      (node (ref "CN204") (pin "2") (pinfunction "2_2") (pintype "passive"))
      (node (ref "CN205") (pin "2") (pinfunction "2_2") (pintype "passive"))
      (node (ref "CN205") (pin "3") (pinfunction "3_3") (pintype "passive"))
      (node (ref "CN207") (pin "2") (pinfunction "2_2") (pintype "passive"))
      (node (ref "D202") (pin "A") (pinfunction "A_A") (pintype "passive"))
      (node (ref "D203") (pin "A") (pinfunction "A_A") (pintype "passive"))
      (node (ref "D204") (pin "A") (pinfunction "A_A") (pintype "passive"))
      (node (ref "J200") (pin "5") (pinfunction "GND_5") (pintype "passive"))
      (node (ref "J200") (pin "Z1") (pinfunction "Shield_Z1") (pintype "passive"))
      (node (ref "J200") (pin "Z2") (pinfunction "Shield_Z2") (pintype "passive"))
      (node (ref "J200") (pin "Z3") (pinfunction "Shield_Z3") (pintype "passive"))
      (node (ref "J200") (pin "Z4") (pinfunction "Shield_Z4") (pintype "passive"))
      (node (ref "Q201") (pin "4") (pinfunction "S_4") (pintype "passive"))
      (node (ref "Q202") (pin "4") (pinfunction "S_4") (pintype "passive"))
      (node (ref "Q204") (pin "4") (pinfunction "S_4") (pintype "passive"))
      (node (ref "Q205") (pin "4") (pinfunction "S_4") (pintype "passive"))
      (node (ref "R202") (pin "1") (pinfunction "1_1") (pintype "passive"))
      (node (ref "R205") (pin "1") (pinfunction "1_1") (pintype "passive"))
      (node (ref "R208") (pin "1") (pinfunction "1_1") (pintype "passive"))
      (node (ref "R210") (pin "2") (pinfunction "2_2") (pintype "passive"))
      (node (ref "R210") (pin "3") (pinfunction "3_3") (pintype "passive"))
      (node (ref "R211") (pin "1") (pinfunction "1_1") (pintype "passive"))
      (node (ref "R215") (pin "1") (pinfunction "1_1") (pintype "passive"))
      (node (ref "R217") (pin "1") (pinfunction "1_1") (pintype "passive"))
      (node (ref "THP202") (pin "1") (pinfunction "1_1") (pintype "passive"))
      (node (ref "THP206") (pin "1") (pinfunction "1_1") (pintype "passive"))
      (node (ref "THP207") (pin "1") (pinfunction "1_1") (pintype "passive"))
      (node (ref "THP208") (pin "1") (pinfunction "1_1") (pintype "passive"))
      (node (ref "THP209") (pin "1") (pinfunction "1_1") (pintype "passive"))
      (node (ref "THP210") (pin "1") (pinfunction "1_1") (pintype "passive"))
      (node (ref "U200") (pin "3") (pinfunction "GND_3") (pintype "passive"))
      (node (ref "U200") (pin "6") (pinfunction "GND_6") (pintype "passive"))
      (node (ref "U201") (pin "2") (pinfunction "GND_2") (pintype "passive"))
      (node (ref "U202") (pin "3") (pinfunction "GND_3") (pintype "passive"))
      (node (ref "U202") (pin "6") (pinfunction "GND_6") (pintype "passive"))
      (node (ref "U203") (pin "2") (pinfunction "GND_2") (pintype "passive"))
      (node (ref "U204") (pin "2") (pinfunction "GND_2") (pintype "passive"))
      (node (ref "U205") (pin "3") (pinfunction "GND_3") (pintype "passive"))
      (node (ref "U205") (pin "6") (pinfunction "GND_6") (pintype "passive"))
      (node (ref "U206") (pin "2") (pinfunction "GND_2") (pintype "passive"))
      (node (ref "U207") (pin "2") (pinfunction "GND_2") (pintype "passive"))
      (node (ref "U208") (pin "2") (pinfunction "GND_2") (pintype "passive"))
    )
    (net (code "12") (name "Net-(CN200-Pad1)") (class "Default")
      (node (ref "CN200") (pin "1") (pinfunction "1_1") (pintype "passive"))
      (node (ref "F202") (pin "1") (pinfunction "1_1") (pintype "passive"))
    )
    (net (code "13") (name "Net-(CN201-Pad1)") (class "Default")
      (node (ref "CN201") (pin "1") (pinfunction "1_1") (pintype "passive"))
      (node (ref "F202") (pin "2") (pinfunction "2_2") (pintype "passive"))
    )
    (net (code "14") (name "Net-(CN202-Pad1)") (class "Default")
      (node (ref "CN202") (pin "1") (pinfunction "1_1") (pintype "passive"))
      (node (ref "F200") (pin "1") (pinfunction "1_1") (pintype "passive"))
    )
    (net (code "15") (name "Net-(CN203-Pad1)") (class "Default")
      (node (ref "CN203") (pin "1") (pinfunction "1_1") (pintype "passive"))
      (node (ref "F200") (pin "2") (pinfunction "2_2") (pintype "passive"))
    )
    (net (code "16") (name "Net-(CN203-Pad2)") (class "Default")
      (node (ref "CN203") (pin "2") (pinfunction "2_2") (pintype "passive"))
      (node (ref "S200") (pin "3") (pinfunction "3_3") (pintype "passive"))
    )
    (net (code "17") (name "Net-(CN204-Pad1)") (class "Default")
      (node (ref "CN204") (pin "1") (pinfunction "1_1") (pintype "passive"))
      (node (ref "F203") (pin "1") (pinfunction "1_1") (pintype "passive"))
    )
    (net (code "18") (name "Net-(CN205-Pad1)") (class "Default")
      (node (ref "CN205") (pin "1") (pinfunction "1_1") (pintype "passive"))
      (node (ref "R206") (pin "2") (pinfunction "2_2") (pintype "passive"))
      (node (ref "THP200") (pin "1") (pinfunction "1_1") (pintype "passive"))
    )
    (net (code "19") (name "Net-(CN206-Pad1)") (class "Default")
      (node (ref "CN206") (pin "1") (pinfunction "1_1") (pintype "passive"))
      (node (ref "F203") (pin "2") (pinfunction "2_2") (pintype "passive"))
    )
    (net (code "20") (name "Net-(D200-A)") (class "Default")
      (node (ref "D200") (pin "1") (pinfunction "A_1") (pintype "passive"))
      (node (ref "D201") (pin "2") (pinfunction "K_2") (pintype "passive"))
      (node (ref "Q202") (pin "1") (pinfunction "D_1") (pintype "passive"))
      (node (ref "Q202") (pin "2") (pinfunction "D_2") (pintype "passive"))
      (node (ref "Q202") (pin "5") (pinfunction "D_5") (pintype "passive"))
      (node (ref "Q202") (pin "6") (pinfunction "D_6") (pintype "passive"))
      (node (ref "R201") (pin "1") (pinfunction "1_1") (pintype "passive"))
      (node (ref "R203") (pin "1") (pinfunction "1_1") (pintype "passive"))
      (node (ref "R204") (pin "1") (pinfunction "1_1") (pintype "passive"))
    )
    (net (code "21") (name "Net-(D200-K)") (class "Default")
      (node (ref "D200") (pin "2") (pinfunction "K_2") (pintype "passive"))
      (node (ref "Q200") (pin "1") (pinfunction "G_1") (pintype "passive"))
      (node (ref "R203") (pin "2") (pinfunction "2_2") (pintype "passive"))
    )
    (net (code "22") (name "Net-(D201-A)") (class "Default")
      (node (ref "D201") (pin "1") (pinfunction "A_1") (pintype "passive"))
      (node (ref "Q201") (pin "3") (pinfunction "G_3") (pintype "passive"))
      (node (ref "R204") (pin "2") (pinfunction "2_2") (pintype "passive"))
    )
    (net (code "23") (name "Net-(D202-K)") (class "Default")
      (node (ref "D202") (pin "C") (pinfunction "K_C") (pintype "passive"))
      (node (ref "F201") (pin "2") (pinfunction "2_2") (pintype "passive"))
      (node (ref "J200") (pin "1") (pinfunction "VBUS_1") (pintype "passive"))
    )
    (net (code "24") (name "Net-(D205-A)") (class "Default")
      (node (ref "D205") (pin "1") (pinfunction "A_1") (pintype "passive"))
      (node (ref "D206") (pin "2") (pinfunction "K_2") (pintype "passive"))
      (node (ref "Q205") (pin "1") (pinfunction "D_1") (pintype "passive"))
      (node (ref "Q205") (pin "2") (pinfunction "D_2") (pintype "passive"))
      (node (ref "Q205") (pin "5") (pinfunction "D_5") (pintype "passive"))
      (node (ref "Q205") (pin "6") (pinfunction "D_6") (pintype "passive"))
      (node (ref "R209") (pin "1") (pinfunction "1_1") (pintype "passive"))
      (node (ref "R212") (pin "1") (pinfunction "1_1") (pintype "passive"))
      (node (ref "R213") (pin "1") (pinfunction "1_1") (pintype "passive"))
    )
    (net (code "25") (name "Net-(D205-K)") (class "Default")
      (node (ref "D205") (pin "2") (pinfunction "K_2") (pintype "passive"))
      (node (ref "Q203") (pin "1") (pinfunction "G_1") (pintype "passive"))
      (node (ref "R212") (pin "2") (pinfunction "2_2") (pintype "passive"))
    )
    (net (code "26") (name "Net-(D206-A)") (class "Default")
      (node (ref "D206") (pin "1") (pinfunction "A_1") (pintype "passive"))
      (node (ref "Q204") (pin "3") (pinfunction "G_3") (pintype "passive"))
      (node (ref "R213") (pin "2") (pinfunction "2_2") (pintype "passive"))
    )
    (net (code "27") (name "Net-(L200-Pad2)") (class "Default")
      (node (ref "L200") (pin "2") (pinfunction "2_2") (pintype "passive"))
      (node (ref "S200") (pin "2") (pinfunction "2_2") (pintype "passive"))
    )
    (net (code "28") (name "Net-(U200-ADJ)") (class "Default")
      (node (ref "R200") (pin "2") (pinfunction "2_2") (pintype "passive"))
      (node (ref "R200") (pin "3") (pinfunction "3_3") (pintype "passive"))
      (node (ref "R202") (pin "2") (pinfunction "2_2") (pintype "passive"))
      (node (ref "U200") (pin "5") (pinfunction "ADJ_5") (pintype "passive"))
    )
    (net (code "29") (name "Net-(U200-OUT)") (class "Default")
      (node (ref "C201") (pin "2") (pinfunction "2_2") (pintype "passive"))
      (node (ref "CN201") (pin "3") (pinfunction "3_3") (pintype "passive"))
      (node (ref "R200") (pin "1") (pinfunction "1_1") (pintype "passive"))
      (node (ref "THP204") (pin "1") (pinfunction "1_1") (pintype "passive"))
      (node (ref "TP200") (pin "1") (pinfunction "1_1") (pintype "passive"))
      (node (ref "U200") (pin "4") (pinfunction "OUT_4") (pintype "passive"))
    )
    (net (code "30") (name "Net-(U202-ADJ)") (class "Default")
      (node (ref "R207") (pin "2") (pinfunction "2_2") (pintype "passive"))
      (node (ref "R207") (pin "3") (pinfunction "3_3") (pintype "passive"))
      (node (ref "R211") (pin "2") (pinfunction "2_2") (pintype "passive"))
      (node (ref "U202") (pin "5") (pinfunction "ADJ_5") (pintype "passive"))
    )
    (net (code "31") (name "Net-(U202-OUT)") (class "Default")
      (node (ref "C209") (pin "2") (pinfunction "2_2") (pintype "passive"))
      (node (ref "CN206") (pin "3") (pinfunction "3_3") (pintype "passive"))
      (node (ref "R207") (pin "1") (pinfunction "1_1") (pintype "passive"))
      (node (ref "THP205") (pin "1") (pinfunction "1_1") (pintype "passive"))
      (node (ref "TP205") (pin "1") (pinfunction "1_1") (pintype "passive"))
      (node (ref "U202") (pin "4") (pinfunction "OUT_4") (pintype "passive"))
    )
    (net (code "32") (name "Net-(U203--)") (class "Default")
      (node (ref "R208") (pin "2") (pinfunction "2_2") (pintype "passive"))
      (node (ref "R214") (pin "1") (pinfunction "1_1") (pintype "passive"))
      (node (ref "U203") (pin "4") (pinfunction "-_4") (pintype "passive"))
    )
    (net (code "33") (name "Net-(U203-Out)") (class "Default")
      (node (ref "R206") (pin "1") (pinfunction "1_1") (pintype "passive"))
      (node (ref "R214") (pin "2") (pinfunction "2_2") (pintype "passive"))
      (node (ref "U203") (pin "1") (pinfunction "Out_1") (pintype "passive"))
    )
    (net (code "34") (name "Net-(U205-ADJ)") (class "Default")
      (node (ref "R216") (pin "2") (pinfunction "2_2") (pintype "passive"))
      (node (ref "R216") (pin "3") (pinfunction "3_3") (pintype "passive"))
      (node (ref "R217") (pin "2") (pinfunction "2_2") (pintype "passive"))
      (node (ref "U205") (pin "5") (pinfunction "ADJ_5") (pintype "passive"))
    )
    (net (code "35") (name "VBus") (class "Default")
      (node (ref "CN203") (pin "3") (pinfunction "3_3") (pintype "passive"))
      (node (ref "F201") (pin "1") (pinfunction "1_1") (pintype "passive"))
    )
    (net (code "36") (name "VCC_DUT") (class "Default")
      (node (ref "Q203") (pin "3") (pinfunction "D_3") (pintype "passive"))
      (node (ref "Q204") (pin "1") (pinfunction "D_1") (pintype "passive"))
      (node (ref "Q204") (pin "2") (pinfunction "D_2") (pintype "passive"))
      (node (ref "Q204") (pin "5") (pinfunction "D_5") (pintype "passive"))
      (node (ref "Q204") (pin "6") (pinfunction "D_6") (pintype "passive"))
      (node (ref "TP206") (pin "1") (pinfunction "1_1") (pintype "passive"))
    )
    (net (code "37") (name "VCC_DUT_PERMANENT") (class "Default")
      (node (ref "C210") (pin "2") (pinfunction "2_2") (pintype "passive"))
      (node (ref "CN206") (pin "2") (pinfunction "2_2") (pintype "passive"))
      (node (ref "Q203") (pin "2") (pinfunction "S_2") (pintype "passive"))
      (node (ref "R209") (pin "2") (pinfunction "2_2") (pintype "passive"))
    )
    (net (code "38") (name "VCC_IO_FPGA") (class "Default")
      (node (ref "C218") (pin "2") (pinfunction "2_2") (pintype "passive"))
      (node (ref "R216") (pin "1") (pinfunction "1_1") (pintype "passive"))
      (node (ref "THP203") (pin "1") (pinfunction "1_1") (pintype "passive"))
      (node (ref "U205") (pin "4") (pinfunction "OUT_4") (pintype "passive"))
    )
    (net (code "39") (name "VCC_PLATFORM") (class "Default")
      (node (ref "Q200") (pin "3") (pinfunction "D_3") (pintype "passive"))
      (node (ref "Q201") (pin "1") (pinfunction "D_1") (pintype "passive"))
      (node (ref "Q201") (pin "2") (pinfunction "D_2") (pintype "passive"))
      (node (ref "Q201") (pin "5") (pinfunction "D_5") (pintype "passive"))
      (node (ref "Q201") (pin "6") (pinfunction "D_6") (pintype "passive"))
      (node (ref "TP201") (pin "1") (pinfunction "1_1") (pintype "passive"))
    )
    (net (code "40") (name "VCC_PLATFORM_PERMANENT") (class "Default")
      (node (ref "C202") (pin "2") (pinfunction "2_2") (pintype "passive"))
      (node (ref "CN201") (pin "2") (pinfunction "2_2") (pintype "passive"))
      (node (ref "Q200") (pin "2") (pinfunction "S_2") (pintype "passive"))
      (node (ref "R201") (pin "2") (pinfunction "2_2") (pintype "passive"))
    )
    (net (code "41") (name "Vsupply") (class "Default")
      (node (ref "C200") (pin "2") (pinfunction "2_2") (pintype "passive"))
      (node (ref "C203") (pin "2") (pinfunction "2_2") (pintype "passive"))
      (node (ref "C206") (pin "2") (pinfunction "2_2") (pintype "passive"))
      (node (ref "C208") (pin "2") (pinfunction "2_2") (pintype "passive"))
      (node (ref "C211") (pin "2") (pinfunction "2_2") (pintype "passive"))
      (node (ref "C213") (pin "2") (pinfunction "2_2") (pintype "passive"))
      (node (ref "C215") (pin "2") (pinfunction "2_2") (pintype "passive"))
      (node (ref "C217") (pin "2") (pinfunction "2_2") (pintype "passive"))
      (node (ref "C219") (pin "2") (pinfunction "2_2") (pintype "passive"))
      (node (ref "L200") (pin "1") (pinfunction "1_1") (pintype "passive"))
      (node (ref "TP202") (pin "1") (pinfunction "1_1") (pintype "passive"))
      (node (ref "U200") (pin "1") (pinfunction "EN_1") (pintype "passive"))
      (node (ref "U200") (pin "2") (pinfunction "IN_2") (pintype "passive"))
      (node (ref "U201") (pin "1") (pinfunction "IN_1") (pintype "passive"))
      (node (ref "U201") (pin "3") (pinfunction "EN_3") (pintype "passive"))
      (node (ref "U202") (pin "1") (pinfunction "EN_1") (pintype "passive"))
      (node (ref "U202") (pin "2") (pinfunction "IN_2") (pintype "passive"))
      (node (ref "U204") (pin "1") (pinfunction "IN_1") (pintype "passive"))
      (node (ref "U204") (pin "3") (pinfunction "EN_3") (pintype "passive"))
      (node (ref "U205") (pin "1") (pinfunction "EN_1") (pintype "passive"))
      (node (ref "U205") (pin "2") (pinfunction "IN_2") (pintype "passive"))
      (node (ref "U206") (pin "1") (pinfunction "IN_1") (pintype "passive"))
      (node (ref "U206") (pin "3") (pinfunction "EN_3") (pintype "passive"))
      (node (ref "U207") (pin "1") (pinfunction "IN_1") (pintype "passive"))
      (node (ref "U207") (pin "3") (pinfunction "EN_3") (pintype "passive"))
      (node (ref "U208") (pin "1") (pinfunction "IN_1") (pintype "passive"))
      (node (ref "U208") (pin "3") (pinfunction "EN_3") (pintype "passive"))
    )
    (net (code "42") (name "unconnected-(J200-ID-Pad4)") (class "Default")
      (node (ref "J200") (pin "4") (pinfunction "ID_4") (pintype "passive"))
    )
    (net (code "43") (name "unconnected-(S200-Pad1)") (class "Default")
      (node (ref "S200") (pin "1") (pinfunction "1_1") (pintype "passive"))
    )
    (net (code "44") (name "unconnected-(U201-NC-Pad4)") (class "Default")
      (node (ref "U201") (pin "4") (pinfunction "NC_4") (pintype "passive"))
    )
    (net (code "45") (name "unconnected-(U204-NC-Pad4)") (class "Default")
      (node (ref "U204") (pin "4") (pinfunction "NC_4") (pintype "passive"))
    )
    (net (code "46") (name "unconnected-(U206-NC-Pad4)") (class "Default")
      (node (ref "U206") (pin "4") (pinfunction "NC_4") (pintype "passive"))
    )
    (net (code "47") (name "unconnected-(U207-NC-Pad4)") (class "Default")
      (node (ref "U207") (pin "4") (pinfunction "NC_4") (pintype "passive"))
    )
    (net (code "48") (name "unconnected-(U208-NC-Pad4)") (class "Default")
      (node (ref "U208") (pin "4") (pinfunction "NC_4") (pintype "passive"))
    )
  )
)
